# CH340G_Test.net
KiCad netlist of a schematic drawn in Altium Designer
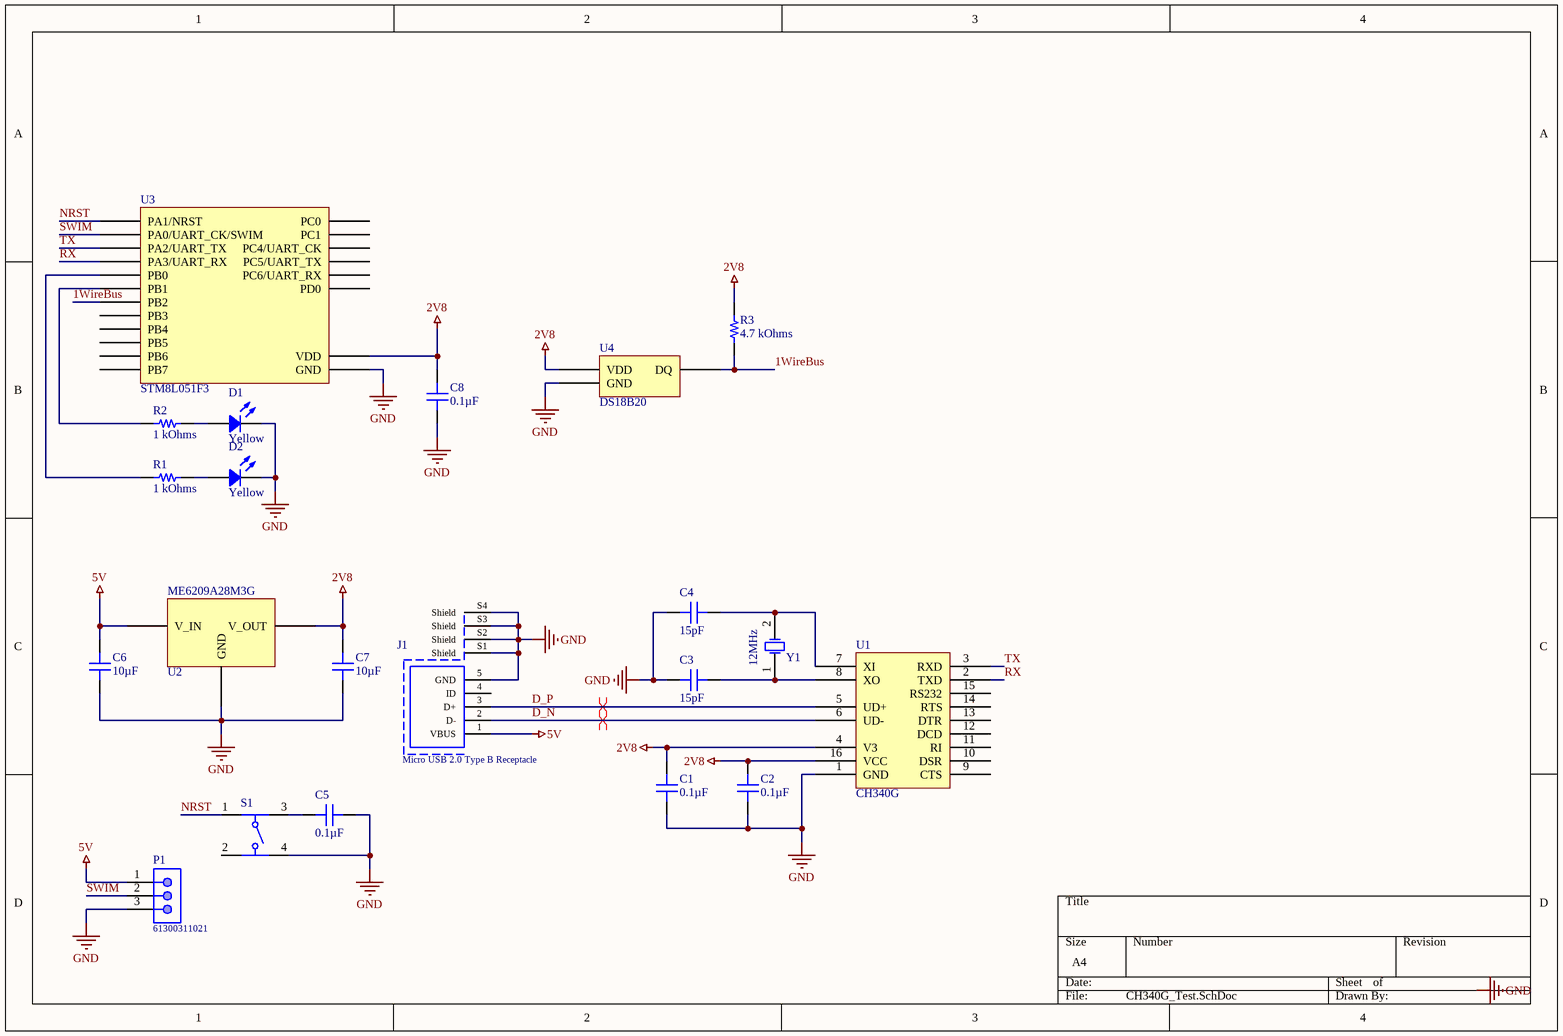
[diagram p0: CH340G_Test.SchDoc]

(export (version "E")
  (design (tool "Eeschema 10.0.6"))
  (components
    (comp (ref "C1")
      (value "0.1µF")
      (footprint "CAP 0805_2012")
      (description "CAP CER 0805 10% X8R 50V 100NF")
      (fields (field (name "PART NUMBER") "AC0805KKX8R9BB104") (field (name "MANUFACTURER") "Yageo"))
      (libsource (lib "Celestial Altium Library - altium_library") (part "Capacitor"))
    )
    (comp (ref "C2")
      (value "0.1µF")
      (footprint "CAP 0805_2012")
      (description "CAP CER 0805 10% X8R 50V 100NF")
      (fields (field (name "PART NUMBER") "AC0805KKX8R9BB104") (field (name "MANUFACTURER") "Yageo"))
      (libsource (lib "Celestial Altium Library - altium_library") (part "Capacitor"))
    )
    (comp (ref "C3")
      (value "15pF")
      (footprint "CAP 0805_2012")
      (description "CAP CER 15PF 25V C0G/NP0 0805")
      (fields (field (name "PART NUMBER") "885012007029") (field (name "MANUFACTURER") "Würth Elektronik"))
      (libsource (lib "Celestial Altium Library - altium_library") (part "Capacitor"))
    )
    (comp (ref "C4")
      (value "15pF")
      (footprint "CAP 0805_2012")
      (description "CAP CER 15PF 25V C0G/NP0 0805")
      (fields (field (name "PART NUMBER") "885012007029") (field (name "MANUFACTURER") "Würth Elektronik"))
      (libsource (lib "Celestial Altium Library - altium_library") (part "Capacitor"))
    )
    (comp (ref "C5")
      (value "0.1µF")
      (footprint "CAP 0805_2012")
      (description "CAP CER 0805 10% X8R 50V 100NF")
      (fields (field (name "PART NUMBER") "AC0805KKX8R9BB104") (field (name "MANUFACTURER") "Yageo"))
      (libsource (lib "Celestial Altium Library - altium_library") (part "Capacitor"))
    )
    (comp (ref "C6")
      (value "10µF")
      (footprint "CAP 0805_2012")
      (description "CAP CER 10UF 6.3V X7R 0805")
      (fields (field (name "PART NUMBER") "C0805X106K9RAC7800") (field (name "MANUFACTURER") "KEMET"))
      (libsource (lib "Celestial Altium Library - altium_library") (part "Capacitor"))
    )
    (comp (ref "C7")
      (value "10µF")
      (footprint "CAP 0805_2012")
      (description "CAP CER 10UF 6.3V X7R 0805")
      (fields (field (name "PART NUMBER") "C0805X106K9RAC7800") (field (name "MANUFACTURER") "KEMET"))
      (libsource (lib "Celestial Altium Library - altium_library") (part "Capacitor"))
    )
    (comp (ref "C8")
      (value "0.1µF")
      (footprint "CAP 0805_2012")
      (description "CAP CER 0805 10% X8R 50V 100NF")
      (fields (field (name "PART NUMBER") "AC0805KKX8R9BB104") (field (name "MANUFACTURER") "Yageo"))
      (libsource (lib "Celestial Altium Library - altium_library") (part "Capacitor"))
    )
    (comp (ref "D1")
      (value "Yellow")
      (footprint "LED 0603_1608 YELLOW")
      (description "0603 YELLOW")
      (fields
        (field (name "PART NUMBER") "BL-HKC36D-AV-TRB")
        (field (name "MANUFACTURER") "American Bright Optoelectronics Corporation")
      )
      (libsource (lib "Celestial Altium Library - altium_library") (part "LED"))
    )
    (comp (ref "D2")
      (value "Yellow")
      (footprint "LED 0603_1608 YELLOW")
      (description "0603 YELLOW")
      (fields
        (field (name "PART NUMBER") "BL-HKC36D-AV-TRB")
        (field (name "MANUFACTURER") "American Bright Optoelectronics Corporation")
      )
      (libsource (lib "Celestial Altium Library - altium_library") (part "LED"))
    )
    (comp (ref "J1")
      (value "Micro USB 2.0 Type B Receptacle")
      (footprint "629105136821")
      (description "Micro USB 2.0 Type B, Receptacle, Horizontal, SMT")
      (fields (field (name "PART NUMBER") "629105136821") (field (name "PUBLISHER") "Wurth Elektronik"))
      (libsource (lib "Altium_WR-COM_USB-Connectors (rev19b)") (part "629105136821"))
    )
    (comp (ref "P1")
      (value "61300311021")
      (footprint "61300311021")
      (description "WR-PHD Pin Header, THT, pitch 2.54mm, Single Row, Angled, 3p")
      (fields (field (name "MANUFACTURER") "Wurth Elektronik"))
      (libsource (lib "61300311021_Altium_WR-PHD_rev20a") (part "61300311021"))
    )
    (comp (ref "R1")
      (value "1 kOhms")
      (footprint "RES 0805_2012")
      (description "RES SMD 1K OHM 1% 1/8W 0805")
      (fields (field (name "PART NUMBER") "RCG08051K00FKEA") (field (name "MANUFACTURER") "Vishay Dale"))
      (libsource (lib "Celestial Altium Library - altium_library") (part "Resistor"))
    )
    (comp (ref "R2")
      (value "1 kOhms")
      (footprint "RES 0805_2012")
      (description "RES SMD 1K OHM 1% 1/8W 0805")
      (fields (field (name "PART NUMBER") "RCG08051K00FKEA") (field (name "MANUFACTURER") "Vishay Dale"))
      (libsource (lib "Celestial Altium Library - altium_library") (part "Resistor"))
    )
    (comp (ref "R3")
      (value "4.7 kOhms")
      (footprint "RES 0805_2012")
      (description "RES SMD 4.7K OHM 5% 0.4W 0805")
      (fields (field (name "PART NUMBER") "RCS08054K70JNEA") (field (name "MANUFACTURER") "Vishay Dale"))
      (libsource (lib "Celestial Altium Library - altium_library") (part "Resistor"))
    )
    (comp (ref "S1")
      (value "~")
      (footprint "4301x60507x6")
      (description "WS-TATV THT Tact Switch 6x6mm, height 5mm, 260gf")
      (fields (field (name "PART NUMBER") "430156050726") (field (name "PUBLISHER") "Wurth Elektronik"))
      (libsource (lib "430186043716_Altium_WS-TATV_rev19a") (part "430156050726"))
    )
    (comp (ref "U1") (value "CH340G") (footprint "CH340G") (libsource (lib "CH340G") (part "CH340G")))
    (comp (ref "U2")
      (value "ME6209A28M3G")
      (footprint "SOT95P285X150-3N")
      (libsource (lib "ME6209") (part "ME6209"))
    )
    (comp (ref "U3")
      (value "STM8L051F3")
      (footprint "TSOP65P630X120-20N")
      (libsource (lib "STM8L051F3") (part "STM8L051F3"))
    )
    (comp (ref "U4") (value "DS18B20") (footprint "DS18B20") (libsource (lib "DS18B20") (part "DS18B20")))
    (comp (ref "Y1")
      (value "12MHz")
      (footprint "WE-XTAL_HC49/4H")
      (description "WE-XTAL Quartz Crystal, size HC49 12MHz")
      (fields (field (name "PART NUMBER") "830014948B") (field (name "PUBLISHER") "Wurth Elektronik"))
      (libsource (lib "Altium_WE-XTAL (rev19a)") (part "830014948B"))
    )
  )
  (nets
    (net (code "1") (name "/1WireBus") (class "Default")
      (node (ref "R3") (pin "1") (pinfunction "1_1") (pintype "passive"))
      (node (ref "U3") (pin "12") (pinfunction "PB2_12") (pintype "passive"))
      (node (ref "U4") (pin "2") (pinfunction "DQ_2") (pintype "passive"))
    )
    (net (code "2") (name "/D_N") (class "Default")
      (node (ref "J1") (pin "2") (pinfunction "D-_2") (pintype "passive"))
      (node (ref "U1") (pin "6") (pinfunction "UD-_6") (pintype "passive"))
    )
    (net (code "3") (name "/D_P") (class "Default")
      (node (ref "J1") (pin "3") (pinfunction "D+_3") (pintype "passive"))
      (node (ref "U1") (pin "5") (pinfunction "UD+_5") (pintype "passive"))
    )
    (net (code "4") (name "/NRST") (class "Default")
      (node (ref "S1") (pin "1") (pinfunction "1_1") (pintype "passive"))
      (node (ref "U3") (pin "4") (pinfunction "PA1/NRST_4") (pintype "passive"))
    )
    (net (code "5") (name "/RX") (class "Default")
      (node (ref "U1") (pin "2") (pinfunction "TXD_2") (pintype "passive"))
      (node (ref "U3") (pin "6") (pinfunction "PA3/UART_RX_6") (pintype "passive"))
    )
    (net (code "6") (name "/SWIM") (class "Default")
      (node (ref "P1") (pin "2") (pinfunction "2_2") (pintype "passive"))
      (node (ref "U3") (pin "3") (pinfunction "PA0/UART_CK/SWIM_3") (pintype "passive"))
    )
    (net (code "7") (name "/TX") (class "Default")
      (node (ref "U1") (pin "3") (pinfunction "RXD_3") (pintype "passive"))
      (node (ref "U3") (pin "5") (pinfunction "PA2/UART_TX_5") (pintype "passive"))
    )
    (net (code "8") (name "2V8") (class "Default")
      (node (ref "C1") (pin "2") (pinfunction "2_2") (pintype "passive"))
      (node (ref "C2") (pin "2") (pinfunction "2_2") (pintype "passive"))
      (node (ref "C7") (pin "2") (pinfunction "2_2") (pintype "passive"))
      (node (ref "C8") (pin "1") (pinfunction "1_1") (pintype "passive"))
      (node (ref "R3") (pin "2") (pinfunction "2_2") (pintype "passive"))
      (node (ref "U1") (pin "16") (pinfunction "VCC_16") (pintype "passive"))
      (node (ref "U1") (pin "4") (pinfunction "V3_4") (pintype "passive"))
      (node (ref "U2") (pin "2") (pinfunction "V_OUT_2") (pintype "passive"))
      (node (ref "U3") (pin "8") (pinfunction "VDD_8") (pintype "passive"))
      (node (ref "U4") (pin "3") (pinfunction "VDD_3") (pintype "power_in"))
    )
    (net (code "9") (name "5V") (class "Default")
      (node (ref "C6") (pin "2") (pinfunction "2_2") (pintype "passive"))
      (node (ref "J1") (pin "1") (pinfunction "VBUS_1") (pintype "passive"))
      (node (ref "P1") (pin "1") (pinfunction "1_1") (pintype "passive"))
      (node (ref "U2") (pin "3") (pinfunction "V_IN_3") (pintype "passive"))
    )
    (net (code "10") (name "GND") (class "Default")
      (node (ref "C1") (pin "1") (pinfunction "1_1") (pintype "passive"))
      (node (ref "C2") (pin "1") (pinfunction "1_1") (pintype "passive"))
      (node (ref "C3") (pin "1") (pinfunction "1_1") (pintype "passive"))
      (node (ref "C4") (pin "1") (pinfunction "1_1") (pintype "passive"))
      (node (ref "C5") (pin "1") (pinfunction "1_1") (pintype "passive"))
      (node (ref "C6") (pin "1") (pinfunction "1_1") (pintype "passive"))
      (node (ref "C7") (pin "1") (pinfunction "1_1") (pintype "passive"))
      (node (ref "C8") (pin "2") (pinfunction "2_2") (pintype "passive"))
      (node (ref "D1") (pin "2") (pinfunction "2_2") (pintype "passive"))
      (node (ref "D2") (pin "2") (pinfunction "2_2") (pintype "passive"))
      (node (ref "J1") (pin "5") (pinfunction "GND_5") (pintype "passive"))
      (node (ref "J1") (pin "S1") (pinfunction "Shield_S1") (pintype "passive"))
      (node (ref "J1") (pin "S2") (pinfunction "Shield_S2") (pintype "passive"))
      (node (ref "J1") (pin "S3") (pinfunction "Shield_S3") (pintype "passive"))
      (node (ref "J1") (pin "S4") (pinfunction "Shield_S4") (pintype "passive"))
      (node (ref "P1") (pin "3") (pinfunction "3_3") (pintype "passive"))
      (node (ref "S1") (pin "4") (pinfunction "4_4") (pintype "passive"))
      (node (ref "U1") (pin "1") (pinfunction "GND_1") (pintype "passive"))
      (node (ref "U2") (pin "1") (pinfunction "GND_1") (pintype "passive"))
      (node (ref "U3") (pin "7") (pinfunction "GND_7") (pintype "passive"))
      (node (ref "U4") (pin "1") (pinfunction "GND_1") (pintype "power_in"))
    )
    (net (code "11") (name "Net-(C5-Pad2)") (class "Default")
      (node (ref "C5") (pin "2") (pinfunction "2_2") (pintype "passive"))
      (node (ref "S1") (pin "3") (pinfunction "3_3") (pintype "passive"))
    )
    (net (code "12") (name "Net-(D1-Pad1)") (class "Default")
      (node (ref "D1") (pin "1") (pinfunction "1_1") (pintype "passive"))
      (node (ref "R2") (pin "2") (pinfunction "2_2") (pintype "passive"))
    )
    (net (code "13") (name "Net-(D2-Pad1)") (class "Default")
      (node (ref "D2") (pin "1") (pinfunction "1_1") (pintype "passive"))
      (node (ref "R1") (pin "2") (pinfunction "2_2") (pintype "passive"))
    )
    (net (code "14") (name "Net-(U1-XI)") (class "Default")
      (node (ref "C4") (pin "2") (pinfunction "2_2") (pintype "passive"))
      (node (ref "U1") (pin "7") (pinfunction "XI_7") (pintype "passive"))
      (node (ref "Y1") (pin "2") (pinfunction "OSC2_2") (pintype "passive"))
    )
    (net (code "15") (name "Net-(U1-XO)") (class "Default")
      (node (ref "C3") (pin "2") (pinfunction "2_2") (pintype "passive"))
      (node (ref "U1") (pin "8") (pinfunction "XO_8") (pintype "passive"))
      (node (ref "Y1") (pin "1") (pinfunction "OSC1_1") (pintype "passive"))
    )
    (net (code "16") (name "Net-(U3-PB0)") (class "Default")
      (node (ref "R1") (pin "1") (pinfunction "1_1") (pintype "passive"))
      (node (ref "U3") (pin "10") (pinfunction "PB0_10") (pintype "passive"))
    )
    (net (code "17") (name "Net-(U3-PB1)") (class "Default")
      (node (ref "R2") (pin "1") (pinfunction "1_1") (pintype "passive"))
      (node (ref "U3") (pin "11") (pinfunction "PB1_11") (pintype "passive"))
    )
    (net (code "18") (name "unconnected-(J1-ID-Pad4)") (class "Default")
      (node (ref "J1") (pin "4") (pinfunction "ID_4") (pintype "passive"))
    )
    (net (code "19") (name "unconnected-(S1-Pad2)") (class "Default")
      (node (ref "S1") (pin "2") (pinfunction "2_2") (pintype "passive"))
    )
    (net (code "20") (name "unconnected-(U1-CTS-Pad9)") (class "Default")
      (node (ref "U1") (pin "9") (pinfunction "CTS_9") (pintype "passive"))
    )
    (net (code "21") (name "unconnected-(U1-DCD-Pad12)") (class "Default")
      (node (ref "U1") (pin "12") (pinfunction "DCD_12") (pintype "passive"))
    )
    (net (code "22") (name "unconnected-(U1-DSR-Pad10)") (class "Default")
      (node (ref "U1") (pin "10") (pinfunction "DSR_10") (pintype "passive"))
    )
    (net (code "23") (name "unconnected-(U1-DTR-Pad13)") (class "Default")
      (node (ref "U1") (pin "13") (pinfunction "DTR_13") (pintype "passive"))
    )
    (net (code "24") (name "unconnected-(U1-RI-Pad11)") (class "Default")
      (node (ref "U1") (pin "11") (pinfunction "RI_11") (pintype "passive"))
    )
    (net (code "25") (name "unconnected-(U1-RS232-Pad15)") (class "Default")
      (node (ref "U1") (pin "15") (pinfunction "RS232_15") (pintype "passive"))
    )
    (net (code "26") (name "unconnected-(U1-RTS-Pad14)") (class "Default")
      (node (ref "U1") (pin "14") (pinfunction "RTS_14") (pintype "passive"))
    )
    (net (code "27") (name "unconnected-(U3-PB3-Pad13)") (class "Default")
      (node (ref "U3") (pin "13") (pinfunction "PB3_13") (pintype "passive"))
    )
    (net (code "28") (name "unconnected-(U3-PB4-Pad14)") (class "Default")
      (node (ref "U3") (pin "14") (pinfunction "PB4_14") (pintype "passive"))
    )
    (net (code "29") (name "unconnected-(U3-PB5-Pad15)") (class "Default")
      (node (ref "U3") (pin "15") (pinfunction "PB5_15") (pintype "passive"))
    )
    (net (code "30") (name "unconnected-(U3-PB6-Pad16)") (class "Default")
      (node (ref "U3") (pin "16") (pinfunction "PB6_16") (pintype "passive"))
    )
    (net (code "31") (name "unconnected-(U3-PB7-Pad17)") (class "Default")
      (node (ref "U3") (pin "17") (pinfunction "PB7_17") (pintype "passive"))
    )
    (net (code "32") (name "unconnected-(U3-PC0-Pad18)") (class "Default")
      (node (ref "U3") (pin "18") (pinfunction "PC0_18") (pintype "passive"))
    )
    (net (code "33") (name "unconnected-(U3-PC1-Pad19)") (class "Default")
      (node (ref "U3") (pin "19") (pinfunction "PC1_19") (pintype "passive"))
    )
    (net (code "34") (name "unconnected-(U3-PC4{slash}UART_CK-Pad20)") (class "Default")
      (node (ref "U3") (pin "20") (pinfunction "PC4/UART_CK_20") (pintype "passive"))
    )
    (net (code "35") (name "unconnected-(U3-PC5{slash}UART_TX-Pad1)") (class "Default")
      (node (ref "U3") (pin "1") (pinfunction "PC5/UART_TX_1") (pintype "passive"))
    )
    (net (code "36") (name "unconnected-(U3-PC6{slash}UART_RX-Pad2)") (class "Default")
      (node (ref "U3") (pin "2") (pinfunction "PC6/UART_RX_2") (pintype "passive"))
    )
    (net (code "37") (name "unconnected-(U3-PD0-Pad9)") (class "Default")
      (node (ref "U3") (pin "9") (pinfunction "PD0_9") (pintype "passive"))
    )
  )
)
